# MODUL_GNU-PI_BRIDGE_V1001.net
KiCad netlist of a schematic drawn in EAGLE
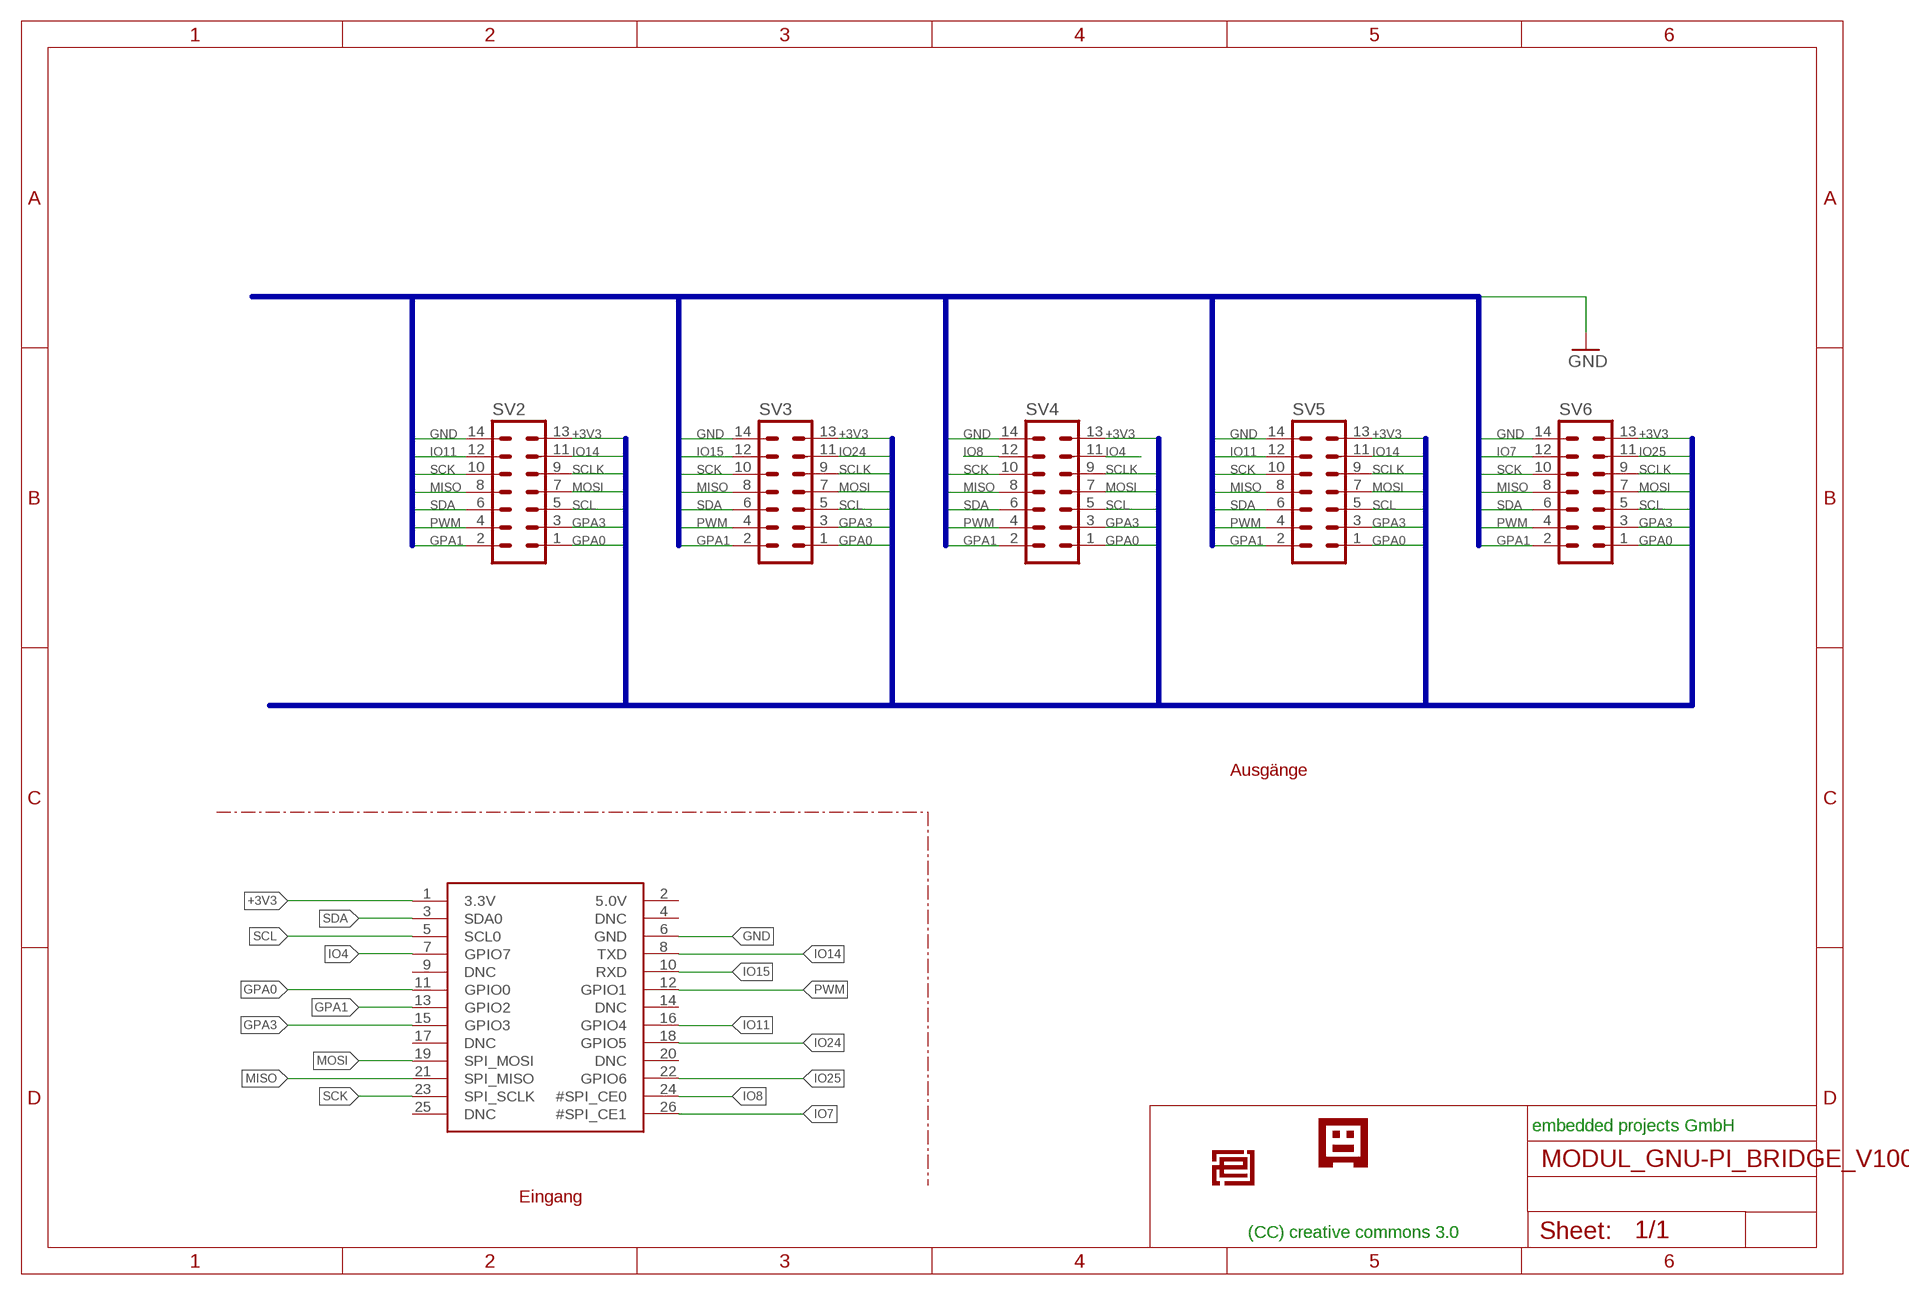
[diagram p0: schematic, sheet 1]

(export (version "E")
  (design (tool "Eeschema 10.0.6"))
  (components
    (comp (ref "SV2")
      (value "ML14")
      (footprint "eagle-import:ML14")
      (libsource (lib "eagle-import") (part "ML14"))
    )
    (comp (ref "SV3")
      (value "ML14")
      (footprint "eagle-import:ML14")
      (libsource (lib "eagle-import") (part "ML14"))
    )
    (comp (ref "SV4")
      (value "ML14")
      (footprint "eagle-import:ML14")
      (libsource (lib "eagle-import") (part "ML14"))
    )
    (comp (ref "SV5")
      (value "ML14")
      (footprint "eagle-import:ML14")
      (libsource (lib "eagle-import") (part "ML14"))
    )
    (comp (ref "SV6")
      (value "ML14")
      (footprint "eagle-import:ML14")
      (libsource (lib "eagle-import") (part "ML14"))
    )
    (comp (ref "U$1")
      (value "RASPBERRYPI_BB")
      (footprint "eagle-import:RASBERRYPI_SHIELD")
      (libsource (lib "eagle-import") (part "RASPBERRYPI_BB"))
    )
    (comp (ref "U$2")
      (value "EPLOGOSIEB")
      (footprint "eagle-import:EPLOGOSIEBDRUCK")
      (libsource (lib "eagle-import") (part "EPLOGOSIEB"))
    )
    (comp (ref "U$3")
      (value "GNUBLINLOGOSIEB")
      (footprint "eagle-import:GNUSIEBDRUCK")
      (libsource (lib "eagle-import") (part "GNUBLINLOGOSIEB"))
    )
  )
  (nets
    (net (code "1") (name "+3V3") (class "Default")
      (node (ref "SV2") (pin "13") (pinfunction "13_13") (pintype "passive"))
      (node (ref "SV3") (pin "13") (pinfunction "13_13") (pintype "passive"))
      (node (ref "SV4") (pin "13") (pinfunction "13_13") (pintype "passive"))
      (node (ref "SV5") (pin "13") (pinfunction "13_13") (pintype "passive"))
      (node (ref "SV6") (pin "13") (pinfunction "13_13") (pintype "passive"))
      (node (ref "U$1") (pin "1") (pinfunction "3.3V_1") (pintype "power_in"))
    )
    (net (code "2") (name "/5.0V") (class "Default")
      (node (ref "U$1") (pin "2") (pinfunction "5.0V_2") (pintype "power_in"))
    )
    (net (code "3") (name "/SCLK") (class "Default")
      (node (ref "SV2") (pin "9") (pinfunction "9_9") (pintype "passive"))
      (node (ref "SV3") (pin "9") (pinfunction "9_9") (pintype "passive"))
      (node (ref "SV4") (pin "9") (pinfunction "9_9") (pintype "passive"))
      (node (ref "SV5") (pin "9") (pinfunction "9_9") (pintype "passive"))
      (node (ref "SV6") (pin "9") (pinfunction "9_9") (pintype "passive"))
    )
    (net (code "4") (name "GND") (class "Default")
      (node (ref "SV2") (pin "14") (pinfunction "14_14") (pintype "passive"))
      (node (ref "SV3") (pin "14") (pinfunction "14_14") (pintype "passive"))
      (node (ref "SV4") (pin "14") (pinfunction "14_14") (pintype "passive"))
      (node (ref "SV5") (pin "14") (pinfunction "14_14") (pintype "passive"))
      (node (ref "SV6") (pin "14") (pinfunction "14_14") (pintype "passive"))
      (node (ref "U$1") (pin "6") (pinfunction "GND_6") (pintype "power_in"))
    )
    (net (code "5") (name "GPA0") (class "Default")
      (node (ref "SV2") (pin "1") (pinfunction "1_1") (pintype "passive"))
      (node (ref "SV3") (pin "1") (pinfunction "1_1") (pintype "passive"))
      (node (ref "SV4") (pin "1") (pinfunction "1_1") (pintype "passive"))
      (node (ref "SV5") (pin "1") (pinfunction "1_1") (pintype "passive"))
      (node (ref "SV6") (pin "1") (pinfunction "1_1") (pintype "passive"))
      (node (ref "U$1") (pin "11") (pinfunction "GPIO0_11") (pintype "bidirectional"))
    )
    (net (code "6") (name "GPA1") (class "Default")
      (node (ref "SV2") (pin "2") (pinfunction "2_2") (pintype "passive"))
      (node (ref "SV3") (pin "2") (pinfunction "2_2") (pintype "passive"))
      (node (ref "SV4") (pin "2") (pinfunction "2_2") (pintype "passive"))
      (node (ref "SV5") (pin "2") (pinfunction "2_2") (pintype "passive"))
      (node (ref "SV6") (pin "2") (pinfunction "2_2") (pintype "passive"))
      (node (ref "U$1") (pin "13") (pinfunction "GPIO2_13") (pintype "bidirectional"))
    )
    (net (code "7") (name "GPA3") (class "Default")
      (node (ref "SV2") (pin "3") (pinfunction "3_3") (pintype "passive"))
      (node (ref "SV3") (pin "3") (pinfunction "3_3") (pintype "passive"))
      (node (ref "SV4") (pin "3") (pinfunction "3_3") (pintype "passive"))
      (node (ref "SV5") (pin "3") (pinfunction "3_3") (pintype "passive"))
      (node (ref "SV6") (pin "3") (pinfunction "3_3") (pintype "passive"))
      (node (ref "U$1") (pin "15") (pinfunction "GPIO3_15") (pintype "bidirectional"))
    )
    (net (code "8") (name "IO4") (class "Default")
      (node (ref "SV4") (pin "11") (pinfunction "11_11") (pintype "passive"))
      (node (ref "U$1") (pin "7") (pinfunction "GPIO7_7") (pintype "bidirectional"))
    )
    (net (code "9") (name "IO7") (class "Default")
      (node (ref "SV6") (pin "12") (pinfunction "12_12") (pintype "passive"))
      (node (ref "U$1") (pin "26") (pinfunction "#SPI_CE1_26") (pintype "output"))
    )
    (net (code "10") (name "IO8") (class "Default")
      (node (ref "SV4") (pin "12") (pinfunction "12_12") (pintype "passive"))
      (node (ref "U$1") (pin "24") (pinfunction "#SPI_CE0_24") (pintype "output"))
    )
    (net (code "11") (name "IO11") (class "Default")
      (node (ref "SV2") (pin "12") (pinfunction "12_12") (pintype "passive"))
      (node (ref "SV5") (pin "12") (pinfunction "12_12") (pintype "passive"))
      (node (ref "U$1") (pin "16") (pinfunction "GPIO4_16") (pintype "bidirectional"))
    )
    (net (code "12") (name "IO14") (class "Default")
      (node (ref "SV2") (pin "11") (pinfunction "11_11") (pintype "passive"))
      (node (ref "SV5") (pin "11") (pinfunction "11_11") (pintype "passive"))
      (node (ref "U$1") (pin "8") (pinfunction "TXD_8") (pintype "output"))
    )
    (net (code "13") (name "IO15") (class "Default")
      (node (ref "SV3") (pin "12") (pinfunction "12_12") (pintype "passive"))
      (node (ref "U$1") (pin "10") (pinfunction "RXD_10") (pintype "input"))
    )
    (net (code "14") (name "IO24") (class "Default")
      (node (ref "SV3") (pin "11") (pinfunction "11_11") (pintype "passive"))
      (node (ref "U$1") (pin "18") (pinfunction "GPIO5_18") (pintype "bidirectional"))
    )
    (net (code "15") (name "IO25") (class "Default")
      (node (ref "SV6") (pin "11") (pinfunction "11_11") (pintype "passive"))
      (node (ref "U$1") (pin "22") (pinfunction "GPIO6_22") (pintype "bidirectional"))
    )
    (net (code "16") (name "MISO") (class "Default")
      (node (ref "SV2") (pin "8") (pinfunction "8_8") (pintype "passive"))
      (node (ref "SV3") (pin "8") (pinfunction "8_8") (pintype "passive"))
      (node (ref "SV4") (pin "8") (pinfunction "8_8") (pintype "passive"))
      (node (ref "SV5") (pin "8") (pinfunction "8_8") (pintype "passive"))
      (node (ref "SV6") (pin "8") (pinfunction "8_8") (pintype "passive"))
      (node (ref "U$1") (pin "21") (pinfunction "SPI_MISO_21") (pintype "input"))
    )
    (net (code "17") (name "MOSI") (class "Default")
      (node (ref "SV2") (pin "7") (pinfunction "7_7") (pintype "passive"))
      (node (ref "SV3") (pin "7") (pinfunction "7_7") (pintype "passive"))
      (node (ref "SV4") (pin "7") (pinfunction "7_7") (pintype "passive"))
      (node (ref "SV5") (pin "7") (pinfunction "7_7") (pintype "passive"))
      (node (ref "SV6") (pin "7") (pinfunction "7_7") (pintype "passive"))
      (node (ref "U$1") (pin "19") (pinfunction "SPI_MOSI_19") (pintype "output"))
    )
    (net (code "18") (name "PWM") (class "Default")
      (node (ref "SV2") (pin "4") (pinfunction "4_4") (pintype "passive"))
      (node (ref "SV3") (pin "4") (pinfunction "4_4") (pintype "passive"))
      (node (ref "SV4") (pin "4") (pinfunction "4_4") (pintype "passive"))
      (node (ref "SV5") (pin "4") (pinfunction "4_4") (pintype "passive"))
      (node (ref "SV6") (pin "4") (pinfunction "4_4") (pintype "passive"))
      (node (ref "U$1") (pin "12") (pinfunction "GPIO1_12") (pintype "bidirectional"))
    )
    (net (code "19") (name "SCK") (class "Default")
      (node (ref "SV2") (pin "10") (pinfunction "10_10") (pintype "passive"))
      (node (ref "SV3") (pin "10") (pinfunction "10_10") (pintype "passive"))
      (node (ref "SV4") (pin "10") (pinfunction "10_10") (pintype "passive"))
      (node (ref "SV5") (pin "10") (pinfunction "10_10") (pintype "passive"))
      (node (ref "SV6") (pin "10") (pinfunction "10_10") (pintype "passive"))
      (node (ref "U$1") (pin "23") (pinfunction "SPI_SCLK_23") (pintype "output"))
    )
    (net (code "20") (name "SCL") (class "Default")
      (node (ref "SV2") (pin "5") (pinfunction "5_5") (pintype "passive"))
      (node (ref "SV3") (pin "5") (pinfunction "5_5") (pintype "passive"))
      (node (ref "SV4") (pin "5") (pinfunction "5_5") (pintype "passive"))
      (node (ref "SV5") (pin "5") (pinfunction "5_5") (pintype "passive"))
      (node (ref "SV6") (pin "5") (pinfunction "5_5") (pintype "passive"))
      (node (ref "U$1") (pin "5") (pinfunction "SCL0_5") (pintype "output"))
    )
    (net (code "21") (name "SDA") (class "Default")
      (node (ref "SV2") (pin "6") (pinfunction "6_6") (pintype "passive"))
      (node (ref "SV3") (pin "6") (pinfunction "6_6") (pintype "passive"))
      (node (ref "SV4") (pin "6") (pinfunction "6_6") (pintype "passive"))
      (node (ref "SV5") (pin "6") (pinfunction "6_6") (pintype "passive"))
      (node (ref "SV6") (pin "6") (pinfunction "6_6") (pintype "passive"))
      (node (ref "U$1") (pin "3") (pinfunction "SDA0_3") (pintype "bidirectional"))
    )
    (net (code "22") (name "unconnected-(U$1-DNC-Pad4)") (class "Default")
      (node (ref "U$1") (pin "4") (pinfunction "DNC_4") (pintype "no_connect"))
    )
    (net (code "23") (name "unconnected-(U$1-DNC-Pad9)") (class "Default")
      (node (ref "U$1") (pin "9") (pinfunction "DNC_9") (pintype "no_connect"))
    )
    (net (code "24") (name "unconnected-(U$1-DNC-Pad14)") (class "Default")
      (node (ref "U$1") (pin "14") (pinfunction "DNC_14") (pintype "no_connect"))
    )
    (net (code "25") (name "unconnected-(U$1-DNC-Pad17)") (class "Default")
      (node (ref "U$1") (pin "17") (pinfunction "DNC_17") (pintype "no_connect"))
    )
    (net (code "26") (name "unconnected-(U$1-DNC-Pad20)") (class "Default")
      (node (ref "U$1") (pin "20") (pinfunction "DNC_20") (pintype "no_connect"))
    )
    (net (code "27") (name "unconnected-(U$1-DNC-Pad25)") (class "Default")
      (node (ref "U$1") (pin "25") (pinfunction "DNC_25") (pintype "no_connect"))
    )
  )
)
